# FXOS8700_with_Extender.net
KiCad netlist of a schematic drawn in EAGLE
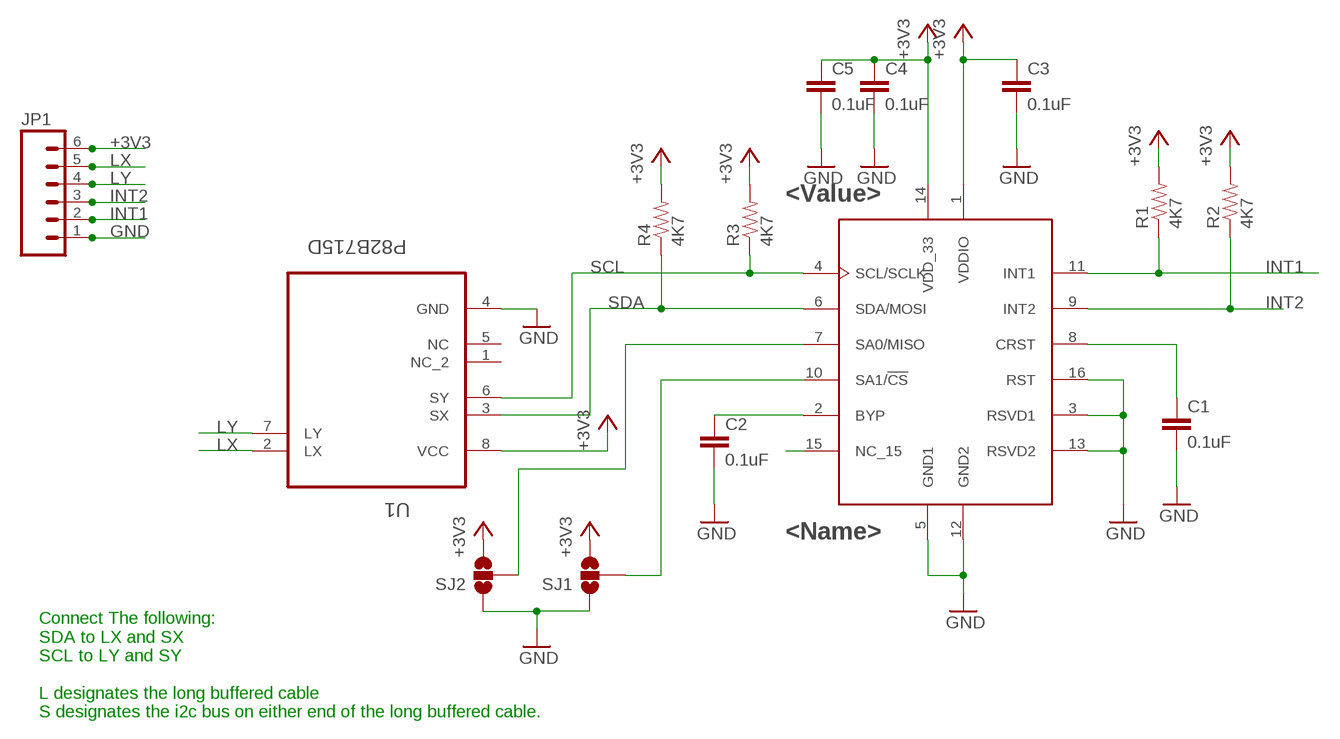
[diagram p0: schematic, sheet 1]

(export (version "E")
  (design (tool "Eeschema 10.0.6"))
  (components
    (comp (ref "C1")
      (value "0.1uF")
      (footprint "eagle-import:0805")
      (libsource (lib "eagle-import") (part "CAP0805"))
    )
    (comp (ref "C2")
      (value "0.1uF")
      (footprint "eagle-import:0805")
      (libsource (lib "eagle-import") (part "CAP0805"))
    )
    (comp (ref "C3")
      (value "0.1uF")
      (footprint "eagle-import:0805")
      (libsource (lib "eagle-import") (part "CAP0805"))
    )
    (comp (ref "C4")
      (value "0.1uF")
      (footprint "eagle-import:0805")
      (libsource (lib "eagle-import") (part "CAP0805"))
    )
    (comp (ref "C5")
      (value "0.1uF")
      (footprint "eagle-import:0805")
      (libsource (lib "eagle-import") (part "CAP0805"))
    )
    (comp (ref "JP1")
      (value "M06LOCK")
      (footprint "eagle-import:1X06_LOCK")
      (libsource (lib "eagle-import") (part "M06LOCK"))
    )
    (comp (ref "R1")
      (value "4K7")
      (footprint "eagle-import:0805")
      (libsource (lib "eagle-import") (part "RESISTOR0805-RES"))
    )
    (comp (ref "R2")
      (value "4K7")
      (footprint "eagle-import:0805")
      (libsource (lib "eagle-import") (part "RESISTOR0805-RES"))
    )
    (comp (ref "R3")
      (value "4K7")
      (footprint "eagle-import:0805")
      (libsource (lib "eagle-import") (part "RESISTOR0805-RES"))
    )
    (comp (ref "R4")
      (value "4K7")
      (footprint "eagle-import:0805")
      (libsource (lib "eagle-import") (part "RESISTOR0805-RES"))
    )
    (comp (ref "SJ1")
      (value "SOLDERJUMPER_2WAYPASTE1&2")
      (footprint "eagle-import:SJ_3_PASTE1&2")
      (libsource (lib "eagle-import") (part "SOLDERJUMPER_2WAYPASTE1&2"))
    )
    (comp (ref "SJ2")
      (value "SOLDERJUMPER_2WAYPASTE1&2")
      (footprint "eagle-import:SJ_3_PASTE1&2")
      (libsource (lib "eagle-import") (part "SOLDERJUMPER_2WAYPASTE1&2"))
    )
    (comp (ref "U$1")
      (value "FXOS870CQ")
      (footprint "eagle-import:QFN16_0P5_3X3")
      (libsource (lib "eagle-import") (part "FXOS870CQ"))
    )
    (comp (ref "U1")
      (value "P82B715D")
      (footprint "eagle-import:SOIC127P600X175-8N")
      (libsource (lib "eagle-import") (part "P82B715D"))
    )
  )
  (nets
    (net (code "1") (name "+3V3") (class "Default")
      (node (ref "C3") (pin "1") (pinfunction "1_1") (pintype "passive"))
      (node (ref "C4") (pin "1") (pinfunction "1_1") (pintype "passive"))
      (node (ref "C5") (pin "1") (pinfunction "1_1") (pintype "passive"))
      (node (ref "JP1") (pin "6") (pinfunction "6_6") (pintype "passive"))
      (node (ref "R1") (pin "2") (pinfunction "2_2") (pintype "passive"))
      (node (ref "R2") (pin "2") (pinfunction "2_2") (pintype "passive"))
      (node (ref "R3") (pin "2") (pinfunction "2_2") (pintype "passive"))
      (node (ref "R4") (pin "2") (pinfunction "2_2") (pintype "passive"))
      (node (ref "SJ1") (pin "3") (pinfunction "3_3") (pintype "passive"))
      (node (ref "SJ2") (pin "3") (pinfunction "3_3") (pintype "passive"))
      (node (ref "U$1") (pin "1") (pinfunction "VDDIO_1") (pintype "power_in"))
      (node (ref "U$1") (pin "14") (pinfunction "VDD_33_14") (pintype "power_in"))
      (node (ref "U1") (pin "8") (pinfunction "VCC_8") (pintype "power_in"))
    )
    (net (code "2") (name "/INT1") (class "Default")
      (node (ref "JP1") (pin "2") (pinfunction "2_2") (pintype "passive"))
      (node (ref "R1") (pin "1") (pinfunction "1_1") (pintype "passive"))
      (node (ref "U$1") (pin "11") (pinfunction "INT1_11") (pintype "output"))
    )
    (net (code "3") (name "/INT2") (class "Default")
      (node (ref "JP1") (pin "3") (pinfunction "3_3") (pintype "passive"))
      (node (ref "R2") (pin "1") (pinfunction "1_1") (pintype "passive"))
      (node (ref "U$1") (pin "9") (pinfunction "INT2_9") (pintype "output"))
    )
    (net (code "4") (name "/LX") (class "Default")
      (node (ref "JP1") (pin "5") (pinfunction "5_5") (pintype "passive"))
      (node (ref "U1") (pin "2") (pinfunction "LX_2") (pintype "output"))
    )
    (net (code "5") (name "/LY") (class "Default")
      (node (ref "JP1") (pin "4") (pinfunction "4_4") (pintype "passive"))
      (node (ref "U1") (pin "7") (pinfunction "LY_7") (pintype "output"))
    )
    (net (code "6") (name "/SCL") (class "Default")
      (node (ref "R3") (pin "1") (pinfunction "1_1") (pintype "passive"))
      (node (ref "U$1") (pin "4") (pinfunction "SCL/SCLK_4") (pintype "bidirectional"))
      (node (ref "U1") (pin "6") (pinfunction "SY_6") (pintype "input"))
    )
    (net (code "7") (name "/SDA") (class "Default")
      (node (ref "R4") (pin "1") (pinfunction "1_1") (pintype "passive"))
      (node (ref "U$1") (pin "6") (pinfunction "SDA/MOSI_6") (pintype "bidirectional"))
      (node (ref "U1") (pin "3") (pinfunction "SX_3") (pintype "input"))
    )
    (net (code "8") (name "GND") (class "Default")
      (node (ref "C1") (pin "2") (pinfunction "2_2") (pintype "passive"))
      (node (ref "C2") (pin "2") (pinfunction "2_2") (pintype "passive"))
      (node (ref "C3") (pin "2") (pinfunction "2_2") (pintype "passive"))
      (node (ref "C4") (pin "2") (pinfunction "2_2") (pintype "passive"))
      (node (ref "C5") (pin "2") (pinfunction "2_2") (pintype "passive"))
      (node (ref "JP1") (pin "1") (pinfunction "1_1") (pintype "passive"))
      (node (ref "SJ1") (pin "1") (pinfunction "1_1") (pintype "passive"))
      (node (ref "SJ2") (pin "1") (pinfunction "1_1") (pintype "passive"))
      (node (ref "U$1") (pin "12") (pinfunction "GND2_12") (pintype "power_in"))
      (node (ref "U$1") (pin "13") (pinfunction "RSVD2_13") (pintype "power_in"))
      (node (ref "U$1") (pin "16") (pinfunction "RST_16") (pintype "input"))
      (node (ref "U$1") (pin "3") (pinfunction "RSVD1_3") (pintype "power_in"))
      (node (ref "U$1") (pin "5") (pinfunction "GND1_5") (pintype "power_in"))
      (node (ref "U1") (pin "4") (pinfunction "GND_4") (pintype "passive"))
    )
    (net (code "9") (name "Net-(U$1-BYP)") (class "Default")
      (node (ref "C2") (pin "1") (pinfunction "1_1") (pintype "passive"))
      (node (ref "U$1") (pin "2") (pinfunction "BYP_2") (pintype "bidirectional"))
    )
    (net (code "10") (name "Net-(U$1-CRST)") (class "Default")
      (node (ref "C1") (pin "1") (pinfunction "1_1") (pintype "passive"))
      (node (ref "U$1") (pin "8") (pinfunction "CRST_8") (pintype "passive"))
    )
    (net (code "11") (name "Net-(U$1-SA0{slash}MISO)") (class "Default")
      (node (ref "SJ2") (pin "2") (pinfunction "2_2") (pintype "passive"))
      (node (ref "U$1") (pin "7") (pinfunction "SA0/MISO_7") (pintype "bidirectional"))
    )
    (net (code "12") (name "Net-(U$1-SA1{slash}~{CS})") (class "Default")
      (node (ref "SJ1") (pin "2") (pinfunction "2_2") (pintype "passive"))
      (node (ref "U$1") (pin "10") (pinfunction "SA1/~{CS}_10") (pintype "bidirectional"))
    )
    (net (code "13") (name "unconnected-(U$1-NC_15-Pad15)") (class "Default")
      (node (ref "U$1") (pin "15") (pinfunction "NC_15_15") (pintype "no_connect"))
    )
    (net (code "14") (name "unconnected-(U1-NC-Pad5)") (class "Default")
      (node (ref "U1") (pin "5") (pinfunction "NC_5") (pintype "no_connect"))
    )
    (net (code "15") (name "unconnected-(U1-NC_2-Pad1)") (class "Default")
      (node (ref "U1") (pin "1") (pinfunction "NC_2_1") (pintype "no_connect"))
    )
  )
)
